# Led_display.net
KiCad netlist of a schematic drawn in EAGLE
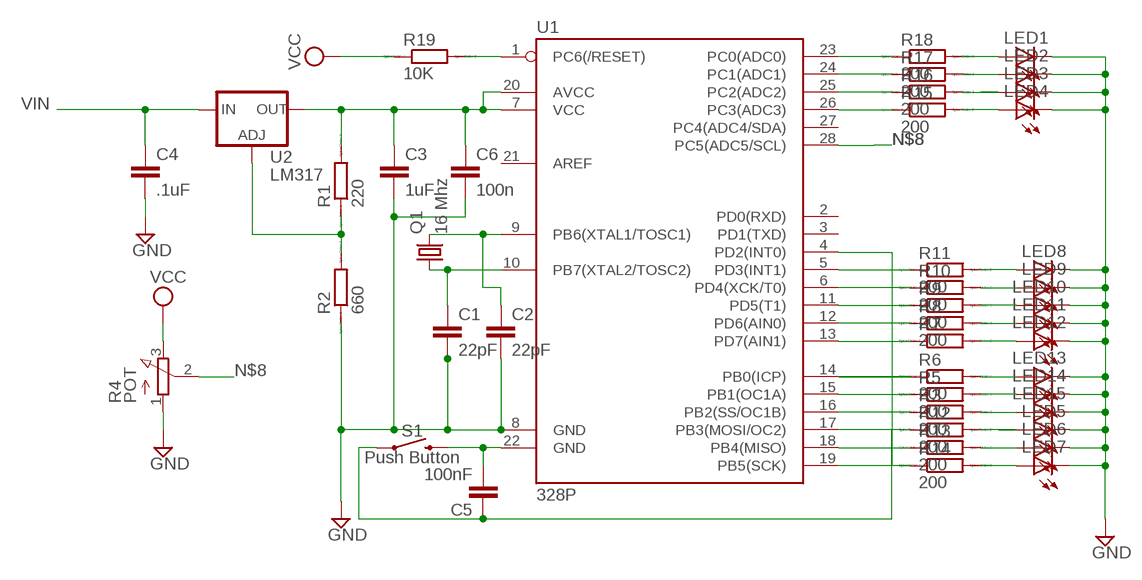
[diagram p0: schematic, sheet 1]

(export (version "E")
  (design (tool "Eeschema 10.0.6"))
  (components
    (comp (ref "C1")
      (value "22pF")
      (footprint "eagle-import:C2.5-3")
      (libsource (lib "eagle-import") (part "C2,5-3"))
    )
    (comp (ref "C2")
      (value "22pF")
      (footprint "eagle-import:C2.5-3")
      (libsource (lib "eagle-import") (part "C2,5-3"))
    )
    (comp (ref "C3")
      (value "1uF")
      (footprint "eagle-import:C2.5-3")
      (libsource (lib "eagle-import") (part "C2,5-3"))
    )
    (comp (ref "C4")
      (value ".1uF")
      (footprint "eagle-import:C2.5-3")
      (libsource (lib "eagle-import") (part "C2,5-3"))
    )
    (comp (ref "C5")
      (value "100nF")
      (footprint "eagle-import:C2.5-3")
      (libsource (lib "eagle-import") (part "C2,5-3"))
    )
    (comp (ref "C6")
      (value "100n")
      (footprint "eagle-import:C2.5-3")
      (libsource (lib "eagle-import") (part "C2,5-3"))
    )
    (comp (ref "LED1")
      (value "LED")
      (footprint "eagle-import:SMARTLED-TTW")
      (libsource (lib "eagle-import") (part "LED"))
    )
    (comp (ref "LED2")
      (value "LED")
      (footprint "eagle-import:SMARTLED-TTW")
      (libsource (lib "eagle-import") (part "LED"))
    )
    (comp (ref "LED3")
      (value "LED")
      (footprint "eagle-import:SMARTLED-TTW")
      (libsource (lib "eagle-import") (part "LED"))
    )
    (comp (ref "LED4")
      (value "LED")
      (footprint "eagle-import:SMARTLED-TTW")
      (libsource (lib "eagle-import") (part "LED"))
    )
    (comp (ref "LED5")
      (value "LED")
      (footprint "eagle-import:SMARTLED-TTW")
      (libsource (lib "eagle-import") (part "LED"))
    )
    (comp (ref "LED6")
      (value "LED")
      (footprint "eagle-import:SMARTLED-TTW")
      (libsource (lib "eagle-import") (part "LED"))
    )
    (comp (ref "LED7")
      (value "LED")
      (footprint "eagle-import:SMARTLED-TTW")
      (libsource (lib "eagle-import") (part "LED"))
    )
    (comp (ref "LED8")
      (value "LED")
      (footprint "eagle-import:SMARTLED-TTW")
      (libsource (lib "eagle-import") (part "LED"))
    )
    (comp (ref "LED9")
      (value "LED")
      (footprint "eagle-import:SMARTLED-TTW")
      (libsource (lib "eagle-import") (part "LED"))
    )
    (comp (ref "LED10")
      (value "LED")
      (footprint "eagle-import:SMARTLED-TTW")
      (libsource (lib "eagle-import") (part "LED"))
    )
    (comp (ref "LED11")
      (value "LED")
      (footprint "eagle-import:SMARTLED-TTW")
      (libsource (lib "eagle-import") (part "LED"))
    )
    (comp (ref "LED12")
      (value "LED")
      (footprint "eagle-import:SMARTLED-TTW")
      (libsource (lib "eagle-import") (part "LED"))
    )
    (comp (ref "LED13")
      (value "LED")
      (footprint "eagle-import:SMARTLED-TTW")
      (libsource (lib "eagle-import") (part "LED"))
    )
    (comp (ref "LED14")
      (value "LED")
      (footprint "eagle-import:SMARTLED-TTW")
      (libsource (lib "eagle-import") (part "LED"))
    )
    (comp (ref "LED15")
      (value "LED")
      (footprint "eagle-import:SMARTLED-TTW")
      (libsource (lib "eagle-import") (part "LED"))
    )
    (comp (ref "Q1")
      (value "16 Mhz")
      (footprint "eagle-import:HC18U-V")
      (libsource (lib "eagle-import") (part "CRYSTALHC18U-V"))
    )
    (comp (ref "R1")
      (value "220")
      (footprint "eagle-import:R2010")
      (libsource (lib "eagle-import") (part "RR2010"))
    )
    (comp (ref "R2")
      (value "660")
      (footprint "eagle-import:R2010")
      (libsource (lib "eagle-import") (part "RR2010"))
    )
    (comp (ref "R3")
      (value "200")
      (footprint "eagle-import:R0805")
      (libsource (lib "eagle-import") (part "R"))
    )
    (comp (ref "R4")
      (value "POT")
      (footprint "eagle-import:3RP_1610N")
      (libsource (lib "eagle-import") (part "3RP/1610N"))
    )
    (comp (ref "R5")
      (value "200")
      (footprint "eagle-import:R0805")
      (libsource (lib "eagle-import") (part "R"))
    )
    (comp (ref "R6")
      (value "200")
      (footprint "eagle-import:R0805")
      (libsource (lib "eagle-import") (part "R"))
    )
    (comp (ref "R7") (value "R") (footprint "eagle-import:R0805") (libsource (lib "eagle-import") (part "R")))
    (comp (ref "R8")
      (value "200")
      (footprint "eagle-import:R0805")
      (libsource (lib "eagle-import") (part "R"))
    )
    (comp (ref "R9")
      (value "200")
      (footprint "eagle-import:R0805")
      (libsource (lib "eagle-import") (part "R"))
    )
    (comp (ref "R10")
      (value "200")
      (footprint "eagle-import:R0805")
      (libsource (lib "eagle-import") (part "R"))
    )
    (comp (ref "R11")
      (value "200")
      (footprint "eagle-import:R0805")
      (libsource (lib "eagle-import") (part "R"))
    )
    (comp (ref "R12")
      (value "200")
      (footprint "eagle-import:R0805")
      (libsource (lib "eagle-import") (part "R"))
    )
    (comp (ref "R13")
      (value "200")
      (footprint "eagle-import:R0805")
      (libsource (lib "eagle-import") (part "R"))
    )
    (comp (ref "R14")
      (value "200")
      (footprint "eagle-import:R0805")
      (libsource (lib "eagle-import") (part "R"))
    )
    (comp (ref "R15")
      (value "200")
      (footprint "eagle-import:R0805")
      (libsource (lib "eagle-import") (part "R"))
    )
    (comp (ref "R16")
      (value "200")
      (footprint "eagle-import:R0805")
      (libsource (lib "eagle-import") (part "R"))
    )
    (comp (ref "R17")
      (value "200")
      (footprint "eagle-import:R0805")
      (libsource (lib "eagle-import") (part "R"))
    )
    (comp (ref "R18")
      (value "200")
      (footprint "eagle-import:R0805")
      (libsource (lib "eagle-import") (part "R"))
    )
    (comp (ref "R19")
      (value "10K")
      (footprint "eagle-import:R0402")
      (libsource (lib "eagle-import") (part "RR0402"))
    )
    (comp (ref "S1")
      (value "Push Button")
      (footprint "eagle-import:TACTILE_SWITCH_PTH_6.0MM")
      (libsource (lib "eagle-import") (part "MOMENTARY-SWITCH-SPST-PTH-6.0MM"))
    )
    (comp (ref "U1")
      (value "328P")
      (footprint "eagle-import:DIP28")
      (libsource (lib "eagle-import") (part "ATMEGA328P_PDIP"))
    )
    (comp (ref "U2")
      (value "LM317")
      (footprint "eagle-import:V-REG_DPACK")
      (libsource (lib "eagle-import") (part "V_REG_317DPACK"))
    )
  )
  (nets
    (net (code "1") (name "/N$8") (class "Default")
      (node (ref "R4") (pin "2") (pinfunction "S_2") (pintype "passive"))
      (node (ref "U1") (pin "28") (pinfunction "PC5(ADC5/SCL)_28") (pintype "bidirectional"))
    )
    (net (code "2") (name "/VIN") (class "Default")
      (node (ref "C4") (pin "1") (pinfunction "1_1") (pintype "passive"))
      (node (ref "U2") (pin "3") (pinfunction "IN_3") (pintype "input"))
    )
    (net (code "3") (name "GND") (class "Default")
      (node (ref "C1") (pin "2") (pinfunction "2_2") (pintype "passive"))
      (node (ref "C2") (pin "2") (pinfunction "2_2") (pintype "passive"))
      (node (ref "C3") (pin "2") (pinfunction "2_2") (pintype "passive"))
      (node (ref "C4") (pin "2") (pinfunction "2_2") (pintype "passive"))
      (node (ref "C6") (pin "2") (pinfunction "2_2") (pintype "passive"))
      (node (ref "LED1") (pin "C@1") (pinfunction "C_C@1") (pintype "passive"))
      (node (ref "LED10") (pin "C@1") (pinfunction "C_C@1") (pintype "passive"))
      (node (ref "LED11") (pin "C@1") (pinfunction "C_C@1") (pintype "passive"))
      (node (ref "LED12") (pin "C@1") (pinfunction "C_C@1") (pintype "passive"))
      (node (ref "LED13") (pin "C@1") (pinfunction "C_C@1") (pintype "passive"))
      (node (ref "LED14") (pin "C@1") (pinfunction "C_C@1") (pintype "passive"))
      (node (ref "LED15") (pin "C@1") (pinfunction "C_C@1") (pintype "passive"))
      (node (ref "LED2") (pin "C@1") (pinfunction "C_C@1") (pintype "passive"))
      (node (ref "LED3") (pin "C@1") (pinfunction "C_C@1") (pintype "passive"))
      (node (ref "LED4") (pin "C@1") (pinfunction "C_C@1") (pintype "passive"))
      (node (ref "LED5") (pin "C@1") (pinfunction "C_C@1") (pintype "passive"))
      (node (ref "LED6") (pin "C@1") (pinfunction "C_C@1") (pintype "passive"))
      (node (ref "LED7") (pin "C@1") (pinfunction "C_C@1") (pintype "passive"))
      (node (ref "LED8") (pin "C@1") (pinfunction "C_C@1") (pintype "passive"))
      (node (ref "LED9") (pin "C@1") (pinfunction "C_C@1") (pintype "passive"))
      (node (ref "R2") (pin "1") (pinfunction "1_1") (pintype "passive"))
      (node (ref "R4") (pin "1") (pinfunction "A_1") (pintype "passive"))
      (node (ref "U1") (pin "8") (pinfunction "GND_8") (pintype "bidirectional"))
    )
    (net (code "4") (name "Net-(C5-Pad1)") (class "Default")
      (node (ref "C5") (pin "1") (pinfunction "1_1") (pintype "passive"))
      (node (ref "S1") (pin "1") (pinfunction "1_1") (pintype "passive"))
    )
    (net (code "5") (name "Net-(LED1-A)") (class "Default")
      (node (ref "LED1") (pin "A@1") (pinfunction "A_A@1") (pintype "passive"))
      (node (ref "R18") (pin "2") (pinfunction "2_2") (pintype "passive"))
    )
    (net (code "6") (name "Net-(LED2-A)") (class "Default")
      (node (ref "LED2") (pin "A@1") (pinfunction "A_A@1") (pintype "passive"))
      (node (ref "R17") (pin "2") (pinfunction "2_2") (pintype "passive"))
    )
    (net (code "7") (name "Net-(LED3-A)") (class "Default")
      (node (ref "LED3") (pin "A@1") (pinfunction "A_A@1") (pintype "passive"))
      (node (ref "R16") (pin "2") (pinfunction "2_2") (pintype "passive"))
    )
    (net (code "8") (name "Net-(LED4-A)") (class "Default")
      (node (ref "LED4") (pin "A@1") (pinfunction "A_A@1") (pintype "passive"))
      (node (ref "R15") (pin "2") (pinfunction "2_2") (pintype "passive"))
    )
    (net (code "9") (name "Net-(LED5-A)") (class "Default")
      (node (ref "LED5") (pin "A@1") (pinfunction "A_A@1") (pintype "passive"))
      (node (ref "R12") (pin "2") (pinfunction "2_2") (pintype "passive"))
    )
    (net (code "10") (name "Net-(LED6-A)") (class "Default")
      (node (ref "LED6") (pin "A@1") (pinfunction "A_A@1") (pintype "passive"))
      (node (ref "R13") (pin "2") (pinfunction "2_2") (pintype "passive"))
    )
    (net (code "11") (name "Net-(LED7-A)") (class "Default")
      (node (ref "LED7") (pin "A@1") (pinfunction "A_A@1") (pintype "passive"))
      (node (ref "R14") (pin "2") (pinfunction "2_2") (pintype "passive"))
    )
    (net (code "12") (name "Net-(LED8-A)") (class "Default")
      (node (ref "LED8") (pin "A@1") (pinfunction "A_A@1") (pintype "passive"))
      (node (ref "R11") (pin "2") (pinfunction "2_2") (pintype "passive"))
    )
    (net (code "13") (name "Net-(LED9-A)") (class "Default")
      (node (ref "LED9") (pin "A@1") (pinfunction "A_A@1") (pintype "passive"))
      (node (ref "R10") (pin "2") (pinfunction "2_2") (pintype "passive"))
    )
    (net (code "14") (name "Net-(LED10-A)") (class "Default")
      (node (ref "LED10") (pin "A@1") (pinfunction "A_A@1") (pintype "passive"))
      (node (ref "R9") (pin "2") (pinfunction "2_2") (pintype "passive"))
    )
    (net (code "15") (name "Net-(LED11-A)") (class "Default")
      (node (ref "LED11") (pin "A@1") (pinfunction "A_A@1") (pintype "passive"))
      (node (ref "R8") (pin "2") (pinfunction "2_2") (pintype "passive"))
    )
    (net (code "16") (name "Net-(LED12-A)") (class "Default")
      (node (ref "LED12") (pin "A@1") (pinfunction "A_A@1") (pintype "passive"))
      (node (ref "R7") (pin "2") (pinfunction "2_2") (pintype "passive"))
    )
    (net (code "17") (name "Net-(LED13-A)") (class "Default")
      (node (ref "LED13") (pin "A@1") (pinfunction "A_A@1") (pintype "passive"))
      (node (ref "R6") (pin "2") (pinfunction "2_2") (pintype "passive"))
    )
    (net (code "18") (name "Net-(LED14-A)") (class "Default")
      (node (ref "LED14") (pin "A@1") (pinfunction "A_A@1") (pintype "passive"))
      (node (ref "R5") (pin "2") (pinfunction "2_2") (pintype "passive"))
    )
    (net (code "19") (name "Net-(LED15-A)") (class "Default")
      (node (ref "LED15") (pin "A@1") (pinfunction "A_A@1") (pintype "passive"))
      (node (ref "R3") (pin "2") (pinfunction "2_2") (pintype "passive"))
    )
    (net (code "20") (name "Net-(S1-2)") (class "Default")
      (node (ref "C5") (pin "2") (pinfunction "2_2") (pintype "passive"))
      (node (ref "S1") (pin "3") (pinfunction "2_3") (pintype "passive"))
      (node (ref "U1") (pin "22") (pinfunction "GND_22") (pintype "bidirectional"))
    )
    (net (code "21") (name "Net-(U1-AVCC)") (class "Default")
      (node (ref "C3") (pin "1") (pinfunction "1_1") (pintype "passive"))
      (node (ref "C6") (pin "1") (pinfunction "1_1") (pintype "passive"))
      (node (ref "R1") (pin "2") (pinfunction "2_2") (pintype "passive"))
      (node (ref "U1") (pin "20") (pinfunction "AVCC_20") (pintype "bidirectional"))
      (node (ref "U1") (pin "7") (pinfunction "VCC_7") (pintype "bidirectional"))
      (node (ref "U2") (pin "4") (pinfunction "OUT_4") (pintype "output"))
    )
    (net (code "22") (name "Net-(U1-PB0(ICP))") (class "Default")
      (node (ref "R6") (pin "1") (pinfunction "1_1") (pintype "passive"))
      (node (ref "U1") (pin "14") (pinfunction "PB0(ICP)_14") (pintype "bidirectional"))
    )
    (net (code "23") (name "Net-(U1-PB1(OC1A))") (class "Default")
      (node (ref "R5") (pin "1") (pinfunction "1_1") (pintype "passive"))
      (node (ref "U1") (pin "15") (pinfunction "PB1(OC1A)_15") (pintype "bidirectional"))
    )
    (net (code "24") (name "Net-(U1-PB2(SS{slash}OC1B))") (class "Default")
      (node (ref "R3") (pin "1") (pinfunction "1_1") (pintype "passive"))
      (node (ref "U1") (pin "16") (pinfunction "PB2(SS/OC1B)_16") (pintype "bidirectional"))
    )
    (net (code "25") (name "Net-(U1-PB3(MOSI{slash}OC2))") (class "Default")
      (node (ref "R12") (pin "1") (pinfunction "1_1") (pintype "passive"))
      (node (ref "U1") (pin "17") (pinfunction "PB3(MOSI/OC2)_17") (pintype "bidirectional"))
    )
    (net (code "26") (name "Net-(U1-PB4(MISO))") (class "Default")
      (node (ref "R13") (pin "1") (pinfunction "1_1") (pintype "passive"))
      (node (ref "U1") (pin "18") (pinfunction "PB4(MISO)_18") (pintype "bidirectional"))
    )
    (net (code "27") (name "Net-(U1-PB5(SCK))") (class "Default")
      (node (ref "R14") (pin "1") (pinfunction "1_1") (pintype "passive"))
      (node (ref "U1") (pin "19") (pinfunction "PB5(SCK)_19") (pintype "bidirectional"))
    )
    (net (code "28") (name "Net-(U1-PB6(XTAL1{slash}TOSC1))") (class "Default")
      (node (ref "C2") (pin "1") (pinfunction "1_1") (pintype "passive"))
      (node (ref "Q1") (pin "2") (pinfunction "2_2") (pintype "passive"))
      (node (ref "U1") (pin "9") (pinfunction "PB6(XTAL1/TOSC1)_9") (pintype "bidirectional"))
    )
    (net (code "29") (name "Net-(U1-PB7(XTAL2{slash}TOSC2))") (class "Default")
      (node (ref "C1") (pin "1") (pinfunction "1_1") (pintype "passive"))
      (node (ref "Q1") (pin "1") (pinfunction "1_1") (pintype "passive"))
      (node (ref "U1") (pin "10") (pinfunction "PB7(XTAL2/TOSC2)_10") (pintype "bidirectional"))
    )
    (net (code "30") (name "Net-(U1-PC0(ADC0))") (class "Default")
      (node (ref "R18") (pin "1") (pinfunction "1_1") (pintype "passive"))
      (node (ref "U1") (pin "23") (pinfunction "PC0(ADC0)_23") (pintype "bidirectional"))
    )
    (net (code "31") (name "Net-(U1-PC1(ADC1))") (class "Default")
      (node (ref "R17") (pin "1") (pinfunction "1_1") (pintype "passive"))
      (node (ref "U1") (pin "24") (pinfunction "PC1(ADC1)_24") (pintype "bidirectional"))
    )
    (net (code "32") (name "Net-(U1-PC2(ADC2))") (class "Default")
      (node (ref "R16") (pin "1") (pinfunction "1_1") (pintype "passive"))
      (node (ref "U1") (pin "25") (pinfunction "PC2(ADC2)_25") (pintype "bidirectional"))
    )
    (net (code "33") (name "Net-(U1-PC3(ADC3))") (class "Default")
      (node (ref "R15") (pin "1") (pinfunction "1_1") (pintype "passive"))
      (node (ref "U1") (pin "26") (pinfunction "PC3(ADC3)_26") (pintype "bidirectional"))
    )
    (net (code "34") (name "Net-(U1-PC6({slash}RESET))") (class "Default")
      (node (ref "R19") (pin "2") (pinfunction "2_2") (pintype "passive"))
      (node (ref "U1") (pin "1") (pinfunction "PC6(/RESET)_1") (pintype "bidirectional"))
    )
    (net (code "35") (name "Net-(U1-PD3(INT1))") (class "Default")
      (node (ref "R11") (pin "1") (pinfunction "1_1") (pintype "passive"))
      (node (ref "U1") (pin "5") (pinfunction "PD3(INT1)_5") (pintype "bidirectional"))
    )
    (net (code "36") (name "Net-(U1-PD4(XCK{slash}T0))") (class "Default")
      (node (ref "R10") (pin "1") (pinfunction "1_1") (pintype "passive"))
      (node (ref "U1") (pin "6") (pinfunction "PD4(XCK/T0)_6") (pintype "bidirectional"))
    )
    (net (code "37") (name "Net-(U1-PD5(T1))") (class "Default")
      (node (ref "R9") (pin "1") (pinfunction "1_1") (pintype "passive"))
      (node (ref "U1") (pin "11") (pinfunction "PD5(T1)_11") (pintype "bidirectional"))
    )
    (net (code "38") (name "Net-(U1-PD6(AIN0))") (class "Default")
      (node (ref "R8") (pin "1") (pinfunction "1_1") (pintype "passive"))
      (node (ref "U1") (pin "12") (pinfunction "PD6(AIN0)_12") (pintype "bidirectional"))
    )
    (net (code "39") (name "Net-(U1-PD7(AIN1))") (class "Default")
      (node (ref "R7") (pin "1") (pinfunction "1_1") (pintype "passive"))
      (node (ref "U1") (pin "13") (pinfunction "PD7(AIN1)_13") (pintype "bidirectional"))
    )
    (net (code "40") (name "Net-(U2-ADJ)") (class "Default")
      (node (ref "R1") (pin "1") (pinfunction "1_1") (pintype "passive"))
      (node (ref "R2") (pin "2") (pinfunction "2_2") (pintype "passive"))
      (node (ref "U2") (pin "1") (pinfunction "ADJ_1") (pintype "input"))
    )
    (net (code "41") (name "VCC") (class "Default")
      (node (ref "R19") (pin "1") (pinfunction "1_1") (pintype "passive"))
      (node (ref "R4") (pin "3") (pinfunction "E_3") (pintype "passive"))
    )
    (net (code "42") (name "unconnected-(U1-AREF-Pad21)") (class "Default")
      (node (ref "U1") (pin "21") (pinfunction "AREF_21") (pintype "bidirectional"))
    )
    (net (code "43") (name "unconnected-(U1-PC4(ADC4{slash}SDA)-Pad27)") (class "Default")
      (node (ref "U1") (pin "27") (pinfunction "PC4(ADC4/SDA)_27") (pintype "bidirectional"))
    )
    (net (code "44") (name "unconnected-(U1-PD0(RXD)-Pad2)") (class "Default")
      (node (ref "U1") (pin "2") (pinfunction "PD0(RXD)_2") (pintype "bidirectional"))
    )
    (net (code "45") (name "unconnected-(U1-PD1(TXD)-Pad3)") (class "Default")
      (node (ref "U1") (pin "3") (pinfunction "PD1(TXD)_3") (pintype "bidirectional"))
    )
    (net (code "46") (name "unconnected-(U1-PD2(INT0)-Pad4)") (class "Default")
      (node (ref "U1") (pin "4") (pinfunction "PD2(INT0)_4") (pintype "bidirectional"))
    )
  )
)
